# 01SignalDetect.net
KiCad netlist of a schematic drawn in Altium Designer
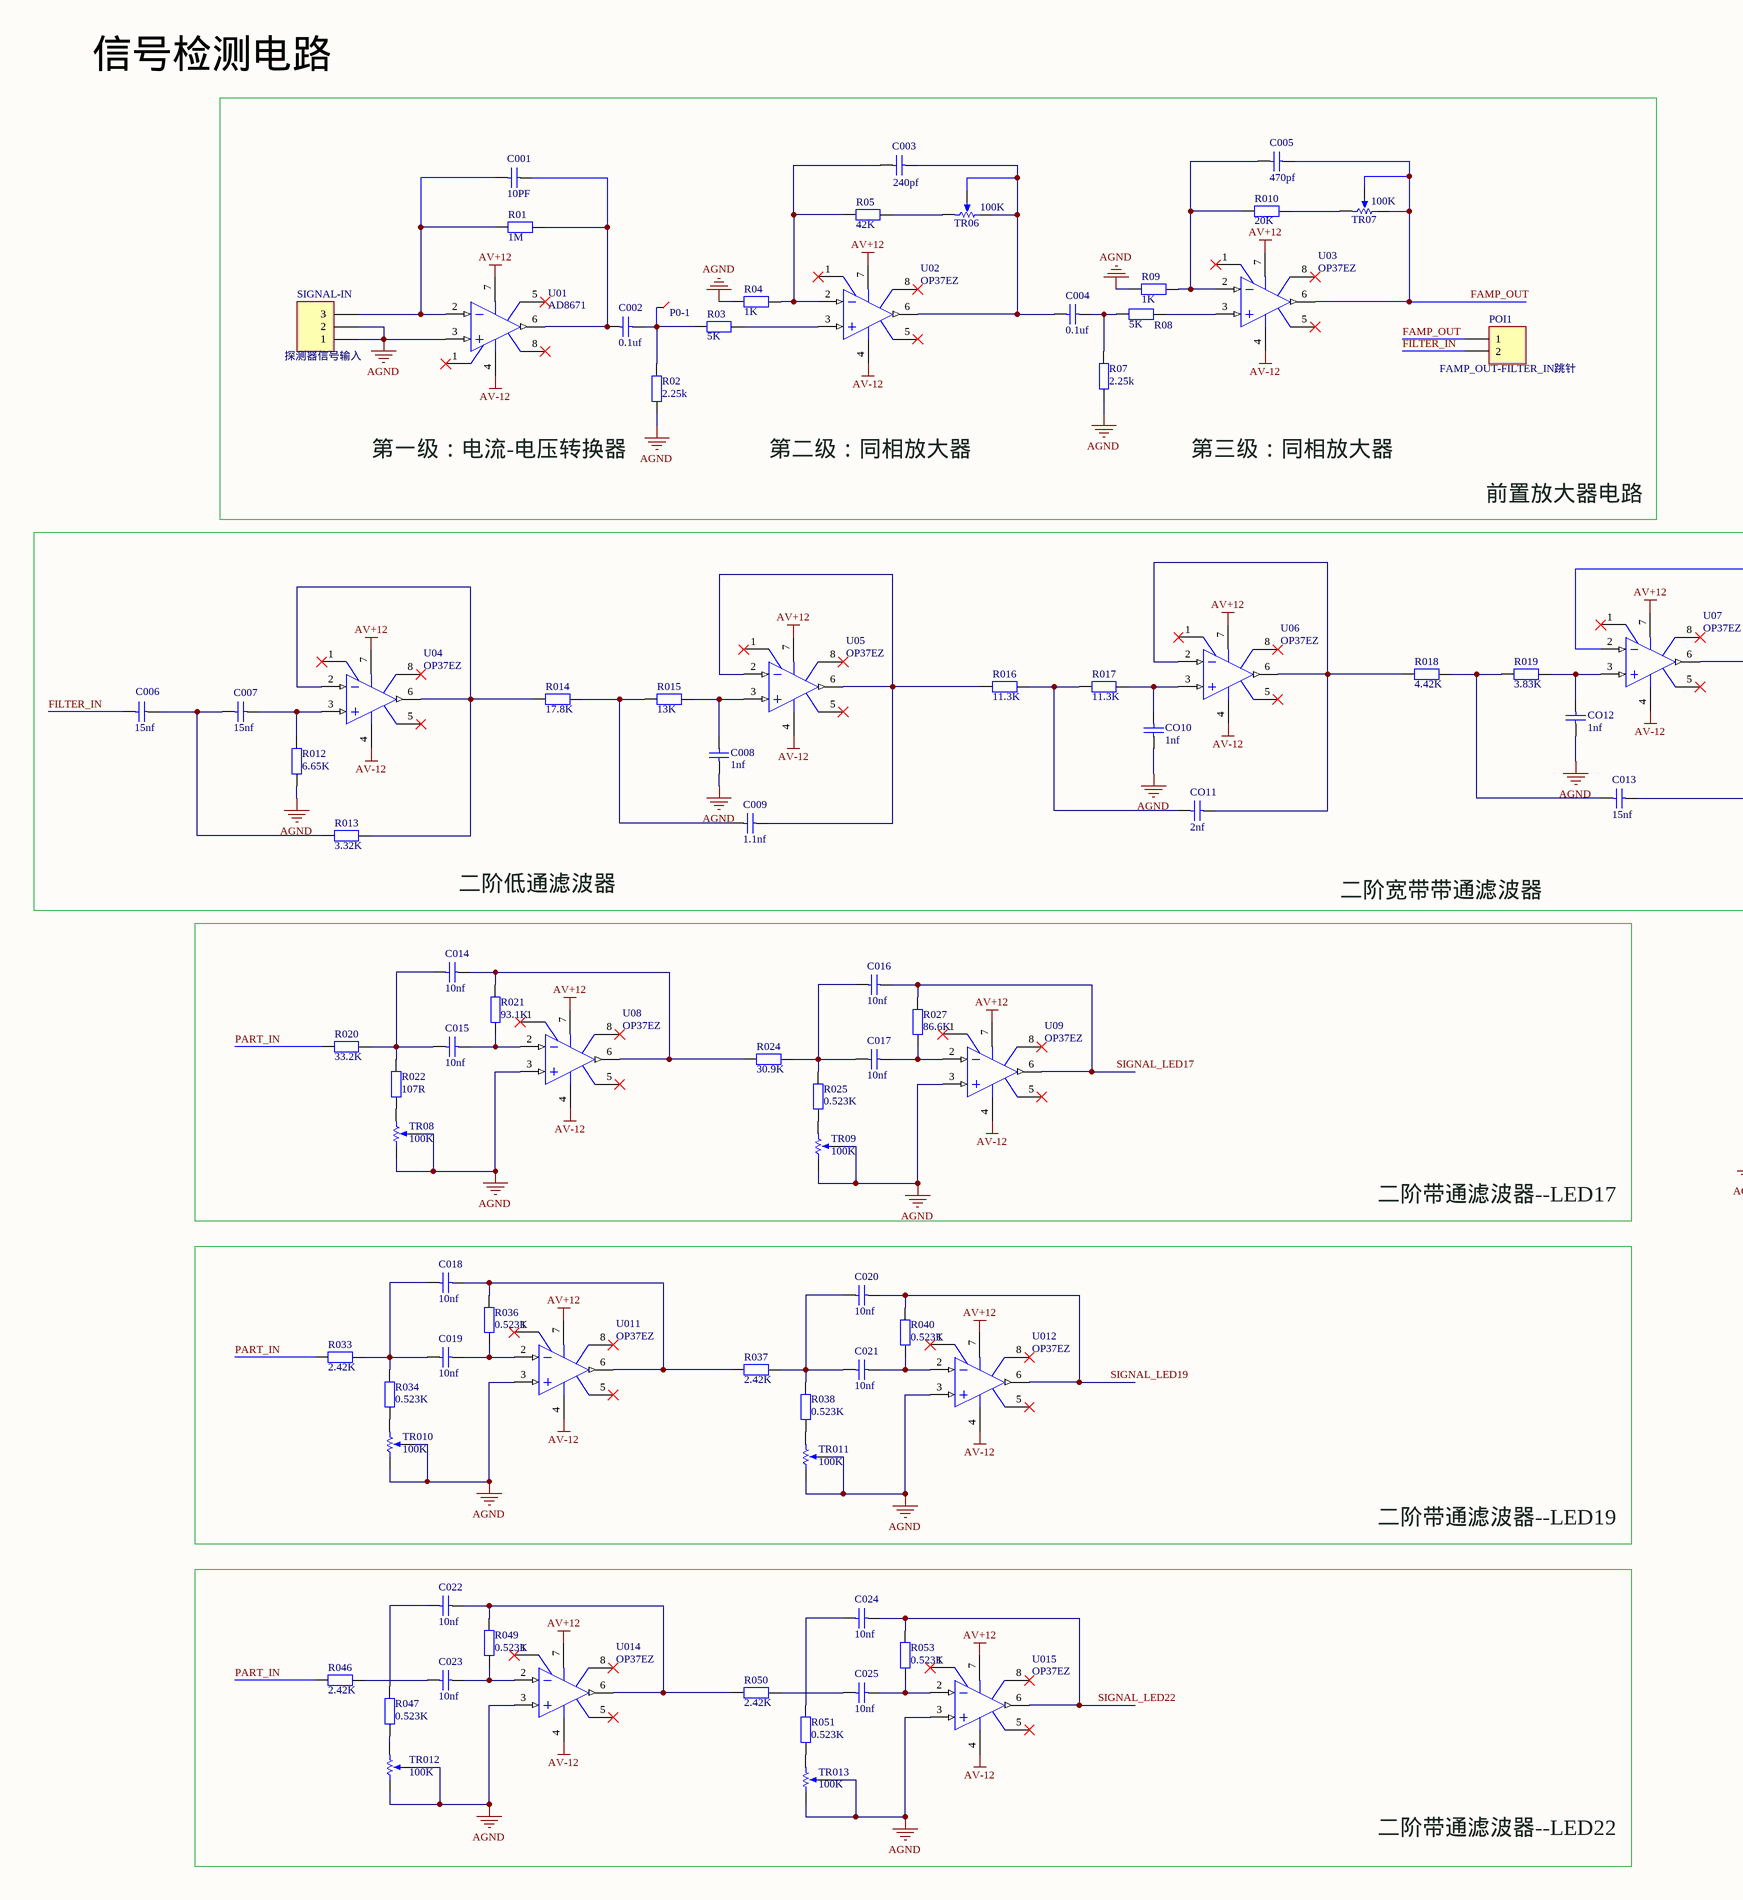
[diagram p0: 01SignalDetect.SchDoc, left]
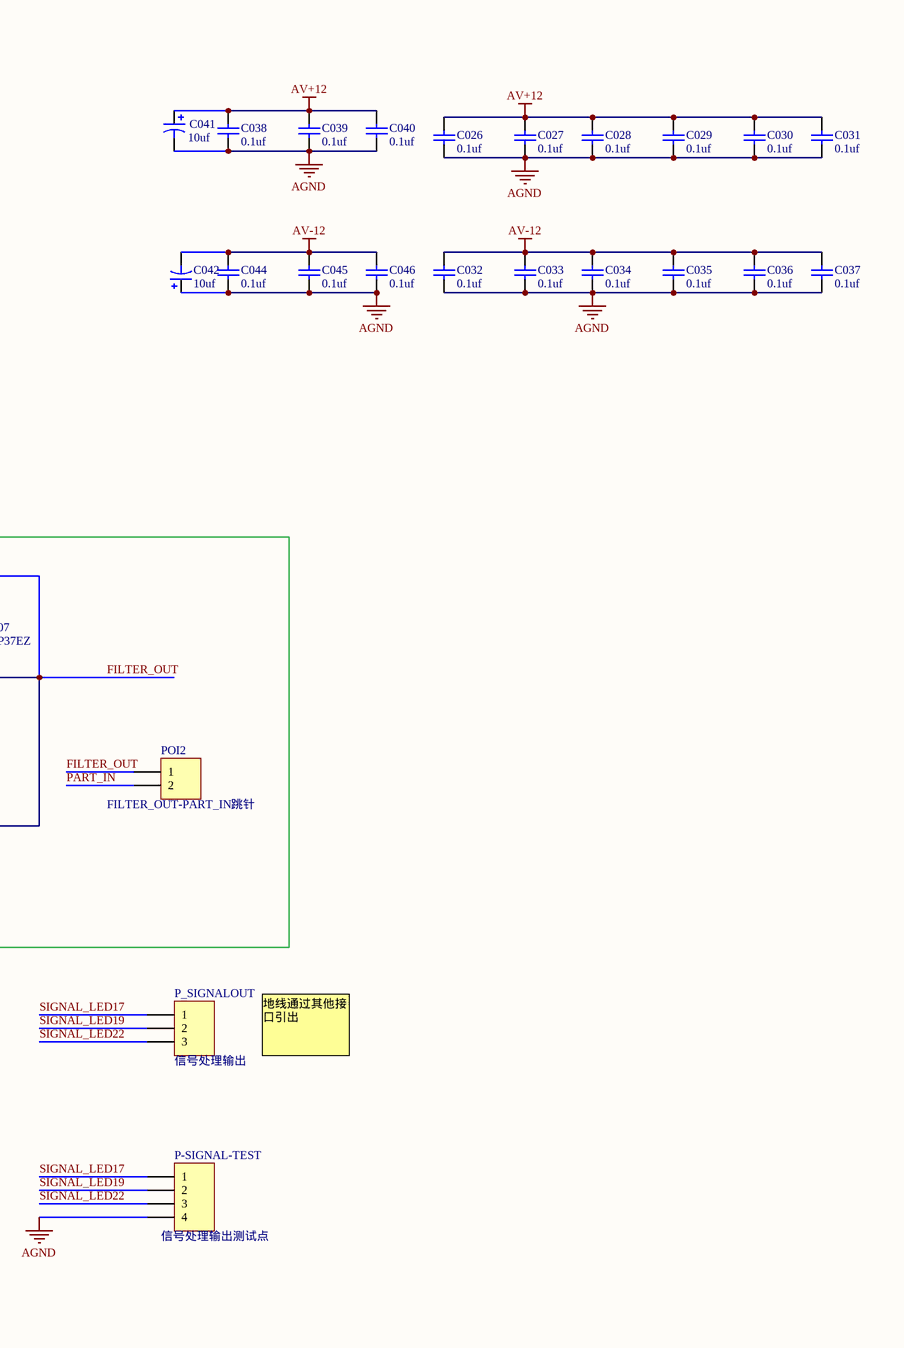
[diagram p1: 01SignalDetect.SchDoc, right]

(export (version "E")
  (design (tool "Eeschema 10.0.6"))
  (components
    (comp (ref "C001")
      (value "10PF")
      (footprint "CC0805")
      (description "Capacitor")
      (fields (field (name "Comment") "Cap"))
      (libsource (lib "Miscellaneous Devices") (part "Cap"))
    )
    (comp (ref "C002")
      (value "0.1uf")
      (footprint "CC0805")
      (description "Capacitor")
      (fields (field (name "Comment") "Cap"))
      (libsource (lib "Miscellaneous Devices") (part "Cap"))
    )
    (comp (ref "C003")
      (value "240pf")
      (footprint "CC0805")
      (description "Capacitor")
      (fields (field (name "Comment") "Cap"))
      (libsource (lib "Miscellaneous Devices") (part "Cap"))
    )
    (comp (ref "C004")
      (value "0.1uf")
      (footprint "CC0805")
      (description "Capacitor")
      (fields (field (name "Comment") "Cap"))
      (libsource (lib "Miscellaneous Devices") (part "Cap"))
    )
    (comp (ref "C005")
      (value "470pf")
      (footprint "CC0805")
      (description "Capacitor")
      (fields (field (name "Comment") "Cap"))
      (libsource (lib "Miscellaneous Devices") (part "Cap"))
    )
    (comp (ref "C006")
      (value "15nf")
      (footprint "CC0805")
      (description "Capacitor")
      (fields (field (name "Comment") "Cap"))
      (libsource (lib "Miscellaneous Devices") (part "Cap"))
    )
    (comp (ref "C007")
      (value "15nf")
      (footprint "CC0805")
      (description "Capacitor")
      (fields (field (name "Comment") "Cap"))
      (libsource (lib "Miscellaneous Devices") (part "Cap"))
    )
    (comp (ref "C008")
      (value "1nf")
      (footprint "CC0805")
      (description "Capacitor")
      (fields (field (name "Comment") "Cap"))
      (libsource (lib "Miscellaneous Devices") (part "Cap"))
    )
    (comp (ref "C009")
      (value "1.1nf")
      (footprint "CC0805")
      (description "Capacitor")
      (fields (field (name "Comment") "Cap"))
      (libsource (lib "Miscellaneous Devices") (part "Cap"))
    )
    (comp (ref "C013")
      (value "15nf")
      (footprint "CC0805")
      (description "Capacitor")
      (fields (field (name "Comment") "Cap"))
      (libsource (lib "Miscellaneous Devices") (part "Cap"))
    )
    (comp (ref "C014")
      (value "10nf")
      (footprint "校正电容")
      (description "Capacitor")
      (fields (field (name "Comment") "Cap"))
      (libsource (lib "Miscellaneous Devices") (part "Cap"))
    )
    (comp (ref "C015")
      (value "10nf")
      (footprint "校正电容")
      (description "Capacitor")
      (fields (field (name "Comment") "Cap"))
      (libsource (lib "Miscellaneous Devices") (part "Cap"))
    )
    (comp (ref "C016")
      (value "10nf")
      (footprint "校正电容")
      (description "Capacitor")
      (fields (field (name "Comment") "Cap"))
      (libsource (lib "Miscellaneous Devices") (part "Cap"))
    )
    (comp (ref "C017")
      (value "10nf")
      (footprint "校正电容")
      (description "Capacitor")
      (fields (field (name "Comment") "Cap"))
      (libsource (lib "Miscellaneous Devices") (part "Cap"))
    )
    (comp (ref "C018")
      (value "10nf")
      (footprint "校正电容")
      (description "Capacitor")
      (fields (field (name "Comment") "Cap"))
      (libsource (lib "Miscellaneous Devices") (part "Cap"))
    )
    (comp (ref "C019")
      (value "10nf")
      (footprint "校正电容")
      (description "Capacitor")
      (fields (field (name "Comment") "Cap"))
      (libsource (lib "Miscellaneous Devices") (part "Cap"))
    )
    (comp (ref "C020")
      (value "10nf")
      (footprint "校正电容")
      (description "Capacitor")
      (fields (field (name "Comment") "Cap"))
      (libsource (lib "Miscellaneous Devices") (part "Cap"))
    )
    (comp (ref "C021")
      (value "10nf")
      (footprint "校正电容")
      (description "Capacitor")
      (fields (field (name "Comment") "Cap"))
      (libsource (lib "Miscellaneous Devices") (part "Cap"))
    )
    (comp (ref "C022")
      (value "10nf")
      (footprint "校正电容")
      (description "Capacitor")
      (fields (field (name "Comment") "Cap"))
      (libsource (lib "Miscellaneous Devices") (part "Cap"))
    )
    (comp (ref "C023")
      (value "10nf")
      (footprint "校正电容")
      (description "Capacitor")
      (fields (field (name "Comment") "Cap"))
      (libsource (lib "Miscellaneous Devices") (part "Cap"))
    )
    (comp (ref "C024")
      (value "10nf")
      (footprint "校正电容")
      (description "Capacitor")
      (fields (field (name "Comment") "Cap"))
      (libsource (lib "Miscellaneous Devices") (part "Cap"))
    )
    (comp (ref "C025")
      (value "10nf")
      (footprint "校正电容")
      (description "Capacitor")
      (fields (field (name "Comment") "Cap"))
      (libsource (lib "Miscellaneous Devices") (part "Cap"))
    )
    (comp (ref "C026")
      (value "0.1uf")
      (footprint "CC0805")
      (description "Capacitor")
      (fields (field (name "Comment") "Cap"))
      (libsource (lib "Miscellaneous Devices") (part "Cap"))
    )
    (comp (ref "C027")
      (value "0.1uf")
      (footprint "CC0805")
      (description "Capacitor")
      (fields (field (name "Comment") "Cap"))
      (libsource (lib "Miscellaneous Devices") (part "Cap"))
    )
    (comp (ref "C028")
      (value "0.1uf")
      (footprint "CC0805")
      (description "Capacitor")
      (fields (field (name "Comment") "Cap"))
      (libsource (lib "Miscellaneous Devices") (part "Cap"))
    )
    (comp (ref "C029")
      (value "0.1uf")
      (footprint "CC0805")
      (description "Capacitor")
      (fields (field (name "Comment") "Cap"))
      (libsource (lib "Miscellaneous Devices") (part "Cap"))
    )
    (comp (ref "C030")
      (value "0.1uf")
      (footprint "CC0805")
      (description "Capacitor")
      (fields (field (name "Comment") "Cap"))
      (libsource (lib "Miscellaneous Devices") (part "Cap"))
    )
    (comp (ref "C031")
      (value "0.1uf")
      (footprint "CC0805")
      (description "Capacitor")
      (fields (field (name "Comment") "Cap"))
      (libsource (lib "Miscellaneous Devices") (part "Cap"))
    )
    (comp (ref "C032")
      (value "0.1uf")
      (footprint "CC0805")
      (description "Capacitor")
      (fields (field (name "Comment") "Cap"))
      (libsource (lib "Miscellaneous Devices") (part "Cap"))
    )
    (comp (ref "C033")
      (value "0.1uf")
      (footprint "CC0805")
      (description "Capacitor")
      (fields (field (name "Comment") "Cap"))
      (libsource (lib "Miscellaneous Devices") (part "Cap"))
    )
    (comp (ref "C034")
      (value "0.1uf")
      (footprint "CC0805")
      (description "Capacitor")
      (fields (field (name "Comment") "Cap"))
      (libsource (lib "Miscellaneous Devices") (part "Cap"))
    )
    (comp (ref "C035")
      (value "0.1uf")
      (footprint "CC0805")
      (description "Capacitor")
      (fields (field (name "Comment") "Cap"))
      (libsource (lib "Miscellaneous Devices") (part "Cap"))
    )
    (comp (ref "C036")
      (value "0.1uf")
      (footprint "CC0805")
      (description "Capacitor")
      (fields (field (name "Comment") "Cap"))
      (libsource (lib "Miscellaneous Devices") (part "Cap"))
    )
    (comp (ref "C037")
      (value "0.1uf")
      (footprint "CC0805")
      (description "Capacitor")
      (fields (field (name "Comment") "Cap"))
      (libsource (lib "Miscellaneous Devices") (part "Cap"))
    )
    (comp (ref "C038")
      (value "0.1uf")
      (footprint "CC0805")
      (description "Capacitor")
      (fields (field (name "Comment") "Cap"))
      (libsource (lib "Miscellaneous Devices") (part "Cap"))
    )
    (comp (ref "C039")
      (value "0.1uf")
      (footprint "CC0805")
      (description "Capacitor")
      (fields (field (name "Comment") "Cap"))
      (libsource (lib "Miscellaneous Devices") (part "Cap"))
    )
    (comp (ref "C040")
      (value "0.1uf")
      (footprint "CC0805")
      (description "Capacitor")
      (fields (field (name "Comment") "Cap"))
      (libsource (lib "Miscellaneous Devices") (part "Cap"))
    )
    (comp (ref "C041")
      (value "10uf")
      (footprint "4*4.5 贴片电解电容")
      (description "Polarized Capacitor (Radial)")
      (fields (field (name "Comment") "Cap Pol1"))
      (libsource (lib "Miscellaneous Devices") (part "Cap Pol1"))
    )
    (comp (ref "C042")
      (value "10uf")
      (footprint "4*4.5 贴片电解电容")
      (description "Polarized Capacitor (Radial)")
      (fields (field (name "Comment") "Cap Pol1"))
      (libsource (lib "Miscellaneous Devices") (part "Cap Pol1"))
    )
    (comp (ref "C044")
      (value "0.1uf")
      (footprint "CC0805")
      (description "Capacitor")
      (fields (field (name "Comment") "Cap"))
      (libsource (lib "Miscellaneous Devices") (part "Cap"))
    )
    (comp (ref "C045")
      (value "0.1uf")
      (footprint "CC0805")
      (description "Capacitor")
      (fields (field (name "Comment") "Cap"))
      (libsource (lib "Miscellaneous Devices") (part "Cap"))
    )
    (comp (ref "C046")
      (value "0.1uf")
      (footprint "CC0805")
      (description "Capacitor")
      (fields (field (name "Comment") "Cap"))
      (libsource (lib "Miscellaneous Devices") (part "Cap"))
    )
    (comp (ref "CO10")
      (value "1nf")
      (footprint "CC0805")
      (description "Capacitor")
      (fields (field (name "Comment") "Cap"))
      (libsource (lib "Miscellaneous Devices") (part "Cap"))
    )
    (comp (ref "CO11")
      (value "2nf")
      (footprint "CC0805")
      (description "Capacitor")
      (fields (field (name "Comment") "Cap"))
      (libsource (lib "Miscellaneous Devices") (part "Cap"))
    )
    (comp (ref "CO12")
      (value "1nf")
      (footprint "CC0805")
      (description "Capacitor")
      (fields (field (name "Comment") "Cap"))
      (libsource (lib "Miscellaneous Devices") (part "Cap"))
    )
    (comp (ref "P-SIGNAL-TEST")
      (value "信号处理输出测试点")
      (footprint "HDR1X4")
      (description "Header, 4-Pin")
      (libsource (lib "Miscellaneous Connectors") (part "Header 4"))
    )
    (comp (ref "P0-1") (value "测试点") (footprint "Text_PAD") (libsource (lib "MY device0") (part "测试点")))
    (comp (ref "POI1")
      (value "FAMP_OUT-FILTER_IN跳针")
      (footprint "HDR1X2")
      (description "Header, 2-Pin")
      (libsource (lib "Miscellaneous Connectors") (part "Header 2"))
    )
    (comp (ref "POI2")
      (value "FILTER_OUT-PART_IN跳针")
      (footprint "HDR1X2")
      (description "Header, 2-Pin")
      (libsource (lib "Miscellaneous Connectors") (part "Header 2"))
    )
    (comp (ref "P_SIGNALOUT")
      (value "信号处理输出")
      (footprint "HDR1X3H")
      (description "Header, 3-Pin, Right Angle")
      (libsource (lib "Miscellaneous Connectors") (part "Header 3H"))
    )
    (comp (ref "R01")
      (value "1M")
      (footprint "0805")
      (description "Resistor")
      (fields (field (name "Comment") "Res2"))
      (libsource (lib "Miscellaneous Devices") (part "Res2"))
    )
    (comp (ref "R02")
      (value "2.25k")
      (footprint "0805")
      (description "Resistor")
      (fields (field (name "Comment") "Res2"))
      (libsource (lib "") (part "Res2_1"))
    )
    (comp (ref "R03")
      (value "5K")
      (footprint "0805")
      (description "Resistor")
      (fields (field (name "Comment") "Res2"))
      (libsource (lib "Miscellaneous Devices") (part "Res2"))
    )
    (comp (ref "R04")
      (value "1K")
      (footprint "0805")
      (description "Resistor")
      (fields (field (name "Comment") "Res2"))
      (libsource (lib "Miscellaneous Devices") (part "Res2"))
    )
    (comp (ref "R05")
      (value "42K")
      (footprint "0805")
      (description "Resistor")
      (fields (field (name "Comment") "Res2"))
      (libsource (lib "Miscellaneous Devices") (part "Res2"))
    )
    (comp (ref "R07")
      (value "2.25k")
      (footprint "0805")
      (description "Resistor")
      (fields (field (name "Comment") "Res2"))
      (libsource (lib "") (part "Res2_1"))
    )
    (comp (ref "R08")
      (value "5K")
      (footprint "0805")
      (description "Resistor")
      (fields (field (name "Comment") "Res2"))
      (libsource (lib "Miscellaneous Devices") (part "Res2"))
    )
    (comp (ref "R09")
      (value "1K")
      (footprint "0805")
      (description "Resistor")
      (fields (field (name "Comment") "Res2"))
      (libsource (lib "Miscellaneous Devices") (part "Res2"))
    )
    (comp (ref "R010")
      (value "20K")
      (footprint "0805")
      (description "Resistor")
      (fields (field (name "Comment") "Res2"))
      (libsource (lib "Miscellaneous Devices") (part "Res2"))
    )
    (comp (ref "R012")
      (value "6.65K")
      (footprint "0805")
      (description "Resistor")
      (fields (field (name "Comment") "Res2"))
      (libsource (lib "") (part "Res2_1"))
    )
    (comp (ref "R013")
      (value "3.32K")
      (footprint "0805")
      (description "Resistor")
      (fields (field (name "Comment") "Res2"))
      (libsource (lib "") (part "Res2_2"))
    )
    (comp (ref "R014")
      (value "17.8K")
      (footprint "0805")
      (description "Resistor")
      (fields (field (name "Comment") "Res2"))
      (libsource (lib "Miscellaneous Devices") (part "Res2"))
    )
    (comp (ref "R015")
      (value "13K")
      (footprint "0805")
      (description "Resistor")
      (fields (field (name "Comment") "Res2"))
      (libsource (lib "") (part "Res2_2"))
    )
    (comp (ref "R016")
      (value "11.3K")
      (footprint "0805")
      (description "Resistor")
      (fields (field (name "Comment") "Res2"))
      (libsource (lib "Miscellaneous Devices") (part "Res2"))
    )
    (comp (ref "R017")
      (value "11.3K")
      (footprint "0805")
      (description "Resistor")
      (fields (field (name "Comment") "Res2"))
      (libsource (lib "Miscellaneous Devices") (part "Res2"))
    )
    (comp (ref "R018")
      (value "4.42K")
      (footprint "0805")
      (description "Resistor")
      (fields (field (name "Comment") "Res2"))
      (libsource (lib "Miscellaneous Devices") (part "Res2"))
    )
    (comp (ref "R019")
      (value "3.83K")
      (footprint "0805")
      (description "Resistor")
      (fields (field (name "Comment") "Res2"))
      (libsource (lib "Miscellaneous Devices") (part "Res2"))
    )
    (comp (ref "R020")
      (value "33.2K")
      (footprint "0805")
      (description "Resistor")
      (fields (field (name "Comment") "Res2"))
      (libsource (lib "Miscellaneous Devices") (part "Res2"))
    )
    (comp (ref "R021")
      (value "93.1K")
      (footprint "0805")
      (description "Resistor")
      (fields (field (name "Comment") "Res2"))
      (libsource (lib "") (part "Res2_1"))
    )
    (comp (ref "R022")
      (value "107R")
      (footprint "0805")
      (description "Resistor")
      (fields (field (name "Comment") "Res2"))
      (libsource (lib "") (part "Res2_1"))
    )
    (comp (ref "R024")
      (value "30.9K")
      (footprint "0805")
      (description "Resistor")
      (fields (field (name "Comment") "Res2"))
      (libsource (lib "Miscellaneous Devices") (part "Res2"))
    )
    (comp (ref "R025")
      (value "0.523K")
      (footprint "0805")
      (description "Resistor")
      (fields (field (name "Comment") "Res2"))
      (libsource (lib "") (part "Res2_1"))
    )
    (comp (ref "R027")
      (value "86.6K")
      (footprint "0805")
      (description "Resistor")
      (fields (field (name "Comment") "Res2"))
      (libsource (lib "") (part "Res2_1"))
    )
    (comp (ref "R033")
      (value "2.42K")
      (footprint "0805")
      (description "Resistor")
      (fields (field (name "Comment") "Res2"))
      (libsource (lib "Miscellaneous Devices") (part "Res2"))
    )
    (comp (ref "R034")
      (value "0.523K")
      (footprint "0805")
      (description "Resistor")
      (fields (field (name "Comment") "Res2"))
      (libsource (lib "") (part "Res2_1"))
    )
    (comp (ref "R036")
      (value "0.523K")
      (footprint "0805")
      (description "Resistor")
      (fields (field (name "Comment") "Res2"))
      (libsource (lib "") (part "Res2_1"))
    )
    (comp (ref "R037")
      (value "2.42K")
      (footprint "0805")
      (description "Resistor")
      (fields (field (name "Comment") "Res2"))
      (libsource (lib "Miscellaneous Devices") (part "Res2"))
    )
    (comp (ref "R038")
      (value "0.523K")
      (footprint "0805")
      (description "Resistor")
      (fields (field (name "Comment") "Res2"))
      (libsource (lib "") (part "Res2_1"))
    )
    (comp (ref "R040")
      (value "0.523K")
      (footprint "0805")
      (description "Resistor")
      (fields (field (name "Comment") "Res2"))
      (libsource (lib "") (part "Res2_1"))
    )
    (comp (ref "R046")
      (value "2.42K")
      (footprint "0805")
      (description "Resistor")
      (fields (field (name "Comment") "Res2"))
      (libsource (lib "Miscellaneous Devices") (part "Res2"))
    )
    (comp (ref "R047")
      (value "0.523K")
      (footprint "0805")
      (description "Resistor")
      (fields (field (name "Comment") "Res2"))
      (libsource (lib "") (part "Res2_1"))
    )
    (comp (ref "R049")
      (value "0.523K")
      (footprint "0805")
      (description "Resistor")
      (fields (field (name "Comment") "Res2"))
      (libsource (lib "") (part "Res2_1"))
    )
    (comp (ref "R050")
      (value "2.42K")
      (footprint "0805")
      (description "Resistor")
      (fields (field (name "Comment") "Res2"))
      (libsource (lib "Miscellaneous Devices") (part "Res2"))
    )
    (comp (ref "R051")
      (value "0.523K")
      (footprint "0805")
      (description "Resistor")
      (fields (field (name "Comment") "Res2"))
      (libsource (lib "") (part "Res2_1"))
    )
    (comp (ref "R053")
      (value "0.523K")
      (footprint "0805")
      (description "Resistor")
      (fields (field (name "Comment") "Res2"))
      (libsource (lib "") (part "Res2_1"))
    )
    (comp (ref "SIGNAL-IN")
      (value "探测器信号输入")
      (footprint "HDR1X3H")
      (description "Header, 3-Pin, Right Angle")
      (libsource (lib "") (part "Header 3H_1"))
    )
    (comp (ref "TR06")
      (value "100K")
      (footprint "VR5")
      (description "Potentiometer")
      (fields (field (name "Comment") "RPot"))
      (libsource (lib "Miscellaneous Devices") (part "RPot"))
    )
    (comp (ref "TR07")
      (value "100K")
      (footprint "VR5")
      (description "Potentiometer")
      (fields (field (name "Comment") "RPot"))
      (libsource (lib "Miscellaneous Devices") (part "RPot"))
    )
    (comp (ref "TR08")
      (value "100K")
      (footprint "VR5")
      (description "Potentiometer")
      (fields (field (name "Comment") "RPot"))
      (libsource (lib "Miscellaneous Devices") (part "RPot"))
    )
    (comp (ref "TR09")
      (value "100K")
      (footprint "VR5")
      (description "Potentiometer")
      (fields (field (name "Comment") "RPot"))
      (libsource (lib "Miscellaneous Devices") (part "RPot"))
    )
    (comp (ref "TR010")
      (value "100K")
      (footprint "VR5")
      (description "Potentiometer")
      (fields (field (name "Comment") "RPot"))
      (libsource (lib "Miscellaneous Devices") (part "RPot"))
    )
    (comp (ref "TR011")
      (value "100K")
      (footprint "VR5")
      (description "Potentiometer")
      (fields (field (name "Comment") "RPot"))
      (libsource (lib "Miscellaneous Devices") (part "RPot"))
    )
    (comp (ref "TR012")
      (value "100K")
      (footprint "VR5")
      (description "Potentiometer")
      (fields (field (name "Comment") "RPot"))
      (libsource (lib "Miscellaneous Devices") (part "RPot"))
    )
    (comp (ref "TR013")
      (value "100K")
      (footprint "VR5")
      (description "Potentiometer")
      (fields (field (name "Comment") "RPot"))
      (libsource (lib "Miscellaneous Devices") (part "RPot"))
    )
    (comp (ref "U01")
      (value "AD8671")
      (footprint "SO-8-N")
      (description "Low-Noise, Precision Operational Amplifier")
      (libsource (lib "AD Operational Amplifier") (part "OP27FJ"))
    )
    (comp (ref "U02")
      (value "OP37EZ")
      (footprint "SO-8-N")
      (description "Low-Noise, Precision, High-Speed Operational Amplifier (Avcl >= 5)")
      (libsource (lib "AD Operational Amplifier") (part "OP37EZ"))
    )
    (comp (ref "U03")
      (value "OP37EZ")
      (footprint "SO-8-N")
      (description "Low-Noise, Precision, High-Speed Operational Amplifier (Avcl >= 5)")
      (libsource (lib "AD Operational Amplifier") (part "OP37EZ"))
    )
    (comp (ref "U04")
      (value "OP37EZ")
      (footprint "SO-8-N")
      (description "Low-Noise, Precision, High-Speed Operational Amplifier (Avcl >= 5)")
      (libsource (lib "AD Operational Amplifier") (part "OP37EZ"))
    )
    (comp (ref "U05")
      (value "OP37EZ")
      (footprint "SO-8-N")
      (description "Low-Noise, Precision, High-Speed Operational Amplifier (Avcl >= 5)")
      (libsource (lib "AD Operational Amplifier") (part "OP37EZ"))
    )
    (comp (ref "U06")
      (value "OP37EZ")
      (footprint "SO-8-N")
      (description "Low-Noise, Precision, High-Speed Operational Amplifier (Avcl >= 5)")
      (libsource (lib "AD Operational Amplifier") (part "OP37EZ"))
    )
    (comp (ref "U07")
      (value "OP37EZ")
      (footprint "SO-8-N")
      (description "Low-Noise, Precision, High-Speed Operational Amplifier (Avcl >= 5)")
      (libsource (lib "AD Operational Amplifier") (part "OP37EZ"))
    )
    (comp (ref "U08")
      (value "OP37EZ")
      (footprint "SO-8-N")
      (description "Low-Noise, Precision, High-Speed Operational Amplifier (Avcl >= 5)")
      (libsource (lib "AD Operational Amplifier") (part "OP37EZ"))
    )
    (comp (ref "U09")
      (value "OP37EZ")
      (footprint "SO-8-N")
      (description "Low-Noise, Precision, High-Speed Operational Amplifier (Avcl >= 5)")
      (libsource (lib "AD Operational Amplifier") (part "OP37EZ"))
    )
    (comp (ref "U011")
      (value "OP37EZ")
      (footprint "SO-8-N")
      (description "Low-Noise, Precision, High-Speed Operational Amplifier (Avcl >= 5)")
      (libsource (lib "AD Operational Amplifier") (part "OP37EZ"))
    )
    (comp (ref "U012")
      (value "OP37EZ")
      (footprint "SO-8-N")
      (description "Low-Noise, Precision, High-Speed Operational Amplifier (Avcl >= 5)")
      (libsource (lib "AD Operational Amplifier") (part "OP37EZ"))
    )
    (comp (ref "U014")
      (value "OP37EZ")
      (footprint "SO-8-N")
      (description "Low-Noise, Precision, High-Speed Operational Amplifier (Avcl >= 5)")
      (libsource (lib "AD Operational Amplifier") (part "OP37EZ"))
    )
    (comp (ref "U015")
      (value "OP37EZ")
      (footprint "SO-8-N")
      (description "Low-Noise, Precision, High-Speed Operational Amplifier (Avcl >= 5)")
      (libsource (lib "AD Operational Amplifier") (part "OP37EZ"))
    )
  )
  (nets
    (net (code "1") (name "/FAMP_OUT") (class "Default")
      (node (ref "C005") (pin "1") (pinfunction "1_1") (pintype "passive"))
      (node (ref "POI1") (pin "1") (pinfunction "1_1") (pintype "passive"))
      (node (ref "TR07") (pin "1") (pinfunction "TOP_1") (pintype "passive"))
      (node (ref "TR07") (pin "2") (pinfunction "TAP_2") (pintype "passive"))
      (node (ref "U03") (pin "6") (pinfunction "OUT_6") (pintype "output"))
    )
    (net (code "2") (name "/FILTER_IN") (class "Default")
      (node (ref "C006") (pin "2") (pinfunction "2_2") (pintype "passive"))
      (node (ref "POI1") (pin "2") (pinfunction "2_2") (pintype "passive"))
    )
    (net (code "3") (name "/FILTER_OUT") (class "Default")
      (node (ref "C013") (pin "1") (pinfunction "1_1") (pintype "passive"))
      (node (ref "POI2") (pin "1") (pinfunction "1_1") (pintype "passive"))
      (node (ref "U07") (pin "2") (pinfunction "IN-_2") (pintype "input"))
      (node (ref "U07") (pin "6") (pinfunction "OUT_6") (pintype "output"))
    )
    (net (code "4") (name "/PART_IN") (class "Default")
      (node (ref "POI2") (pin "2") (pinfunction "2_2") (pintype "passive"))
      (node (ref "R020") (pin "1") (pinfunction "1_1") (pintype "passive"))
      (node (ref "R033") (pin "1") (pinfunction "1_1") (pintype "passive"))
      (node (ref "R046") (pin "1") (pinfunction "1_1") (pintype "passive"))
    )
    (net (code "5") (name "/SIGNAL_LED17") (class "Default")
      (node (ref "C016") (pin "1") (pinfunction "1_1") (pintype "passive"))
      (node (ref "P-SIGNAL-TEST") (pin "1") (pinfunction "1_1") (pintype "passive"))
      (node (ref "P_SIGNALOUT") (pin "1") (pinfunction "1_1") (pintype "passive"))
      (node (ref "R027") (pin "2") (pinfunction "2_2") (pintype "passive"))
      (node (ref "U09") (pin "6") (pinfunction "OUT_6") (pintype "output"))
    )
    (net (code "6") (name "/SIGNAL_LED19") (class "Default")
      (node (ref "C020") (pin "1") (pinfunction "1_1") (pintype "passive"))
      (node (ref "P-SIGNAL-TEST") (pin "2") (pinfunction "2_2") (pintype "passive"))
      (node (ref "P_SIGNALOUT") (pin "2") (pinfunction "2_2") (pintype "passive"))
      (node (ref "R040") (pin "2") (pinfunction "2_2") (pintype "passive"))
      (node (ref "U012") (pin "6") (pinfunction "OUT_6") (pintype "output"))
    )
    (net (code "7") (name "/SIGNAL_LED22") (class "Default")
      (node (ref "C024") (pin "1") (pinfunction "1_1") (pintype "passive"))
      (node (ref "P-SIGNAL-TEST") (pin "3") (pinfunction "3_3") (pintype "passive"))
      (node (ref "P_SIGNALOUT") (pin "3") (pinfunction "3_3") (pintype "passive"))
      (node (ref "R053") (pin "2") (pinfunction "2_2") (pintype "passive"))
      (node (ref "U015") (pin "6") (pinfunction "OUT_6") (pintype "output"))
    )
    (net (code "8") (name "AGND") (class "Default")
      (node (ref "C008") (pin "2") (pinfunction "2_2") (pintype "passive"))
      (node (ref "C026") (pin "2") (pinfunction "2_2") (pintype "passive"))
      (node (ref "C027") (pin "2") (pinfunction "2_2") (pintype "passive"))
      (node (ref "C028") (pin "2") (pinfunction "2_2") (pintype "passive"))
      (node (ref "C029") (pin "2") (pinfunction "2_2") (pintype "passive"))
      (node (ref "C030") (pin "2") (pinfunction "2_2") (pintype "passive"))
      (node (ref "C031") (pin "2") (pinfunction "2_2") (pintype "passive"))
      (node (ref "C032") (pin "2") (pinfunction "2_2") (pintype "passive"))
      (node (ref "C033") (pin "2") (pinfunction "2_2") (pintype "passive"))
      (node (ref "C034") (pin "2") (pinfunction "2_2") (pintype "passive"))
      (node (ref "C035") (pin "2") (pinfunction "2_2") (pintype "passive"))
      (node (ref "C036") (pin "2") (pinfunction "2_2") (pintype "passive"))
      (node (ref "C037") (pin "2") (pinfunction "2_2") (pintype "passive"))
      (node (ref "C038") (pin "2") (pinfunction "2_2") (pintype "passive"))
      (node (ref "C039") (pin "2") (pinfunction "2_2") (pintype "passive"))
      (node (ref "C040") (pin "2") (pinfunction "2_2") (pintype "passive"))
      (node (ref "C041") (pin "2") (pinfunction "2_2") (pintype "passive"))
      (node (ref "C042") (pin "1") (pinfunction "1_1") (pintype "passive"))
      (node (ref "C044") (pin "2") (pinfunction "2_2") (pintype "passive"))
      (node (ref "C045") (pin "2") (pinfunction "2_2") (pintype "passive"))
      (node (ref "C046") (pin "2") (pinfunction "2_2") (pintype "passive"))
      (node (ref "CO10") (pin "1") (pinfunction "1_1") (pintype "passive"))
      (node (ref "CO12") (pin "1") (pinfunction "1_1") (pintype "passive"))
      (node (ref "P-SIGNAL-TEST") (pin "4") (pinfunction "4_4") (pintype "passive"))
      (node (ref "R012") (pin "1") (pinfunction "1_1") (pintype "passive"))
      (node (ref "R02") (pin "1") (pinfunction "1_1") (pintype "passive"))
      (node (ref "R04") (pin "1") (pinfunction "1_1") (pintype "passive"))
      (node (ref "R07") (pin "1") (pinfunction "1_1") (pintype "passive"))
      (node (ref "R09") (pin "1") (pinfunction "1_1") (pintype "passive"))
      (node (ref "SIGNAL-IN") (pin "1") (pinfunction "1_1") (pintype "passive"))
      (node (ref "SIGNAL-IN") (pin "2") (pinfunction "2_2") (pintype "passive"))
      (node (ref "TR010") (pin "1") (pinfunction "TOP_1") (pintype "passive"))
      (node (ref "TR010") (pin "2") (pinfunction "TAP_2") (pintype "passive"))
      (node (ref "TR011") (pin "1") (pinfunction "TOP_1") (pintype "passive"))
      (node (ref "TR011") (pin "2") (pinfunction "TAP_2") (pintype "passive"))
      (node (ref "TR012") (pin "1") (pinfunction "TOP_1") (pintype "passive"))
      (node (ref "TR012") (pin "2") (pinfunction "TAP_2") (pintype "passive"))
      (node (ref "TR013") (pin "1") (pinfunction "TOP_1") (pintype "passive"))
      (node (ref "TR013") (pin "2") (pinfunction "TAP_2") (pintype "passive"))
      (node (ref "TR08") (pin "1") (pinfunction "TOP_1") (pintype "passive"))
      (node (ref "TR08") (pin "2") (pinfunction "TAP_2") (pintype "passive"))
      (node (ref "TR09") (pin "1") (pinfunction "TOP_1") (pintype "passive"))
      (node (ref "TR09") (pin "2") (pinfunction "TAP_2") (pintype "passive"))
      (node (ref "U01") (pin "3") (pinfunction "IN+_3") (pintype "input"))
      (node (ref "U011") (pin "3") (pinfunction "IN+_3") (pintype "input"))
      (node (ref "U012") (pin "3") (pinfunction "IN+_3") (pintype "input"))
      (node (ref "U014") (pin "3") (pinfunction "IN+_3") (pintype "input"))
      (node (ref "U015") (pin "3") (pinfunction "IN+_3") (pintype "input"))
      (node (ref "U08") (pin "3") (pinfunction "IN+_3") (pintype "input"))
      (node (ref "U09") (pin "3") (pinfunction "IN+_3") (pintype "input"))
    )
    (net (code "9") (name "AV+12") (class "Default")
      (node (ref "C026") (pin "1") (pinfunction "1_1") (pintype "passive"))
      (node (ref "C027") (pin "1") (pinfunction "1_1") (pintype "passive"))
      (node (ref "C028") (pin "1") (pinfunction "1_1") (pintype "passive"))
      (node (ref "C029") (pin "1") (pinfunction "1_1") (pintype "passive"))
      (node (ref "C030") (pin "1") (pinfunction "1_1") (pintype "passive"))
      (node (ref "C031") (pin "1") (pinfunction "1_1") (pintype "passive"))
      (node (ref "C038") (pin "1") (pinfunction "1_1") (pintype "passive"))
      (node (ref "C039") (pin "1") (pinfunction "1_1") (pintype "passive"))
      (node (ref "C040") (pin "1") (pinfunction "1_1") (pintype "passive"))
      (node (ref "C041") (pin "1") (pinfunction "1_1") (pintype "passive"))
      (node (ref "U01") (pin "7") (pinfunction "V+_7") (pintype "power_in"))
      (node (ref "U011") (pin "7") (pinfunction "V+_7") (pintype "power_in"))
      (node (ref "U012") (pin "7") (pinfunction "V+_7") (pintype "power_in"))
      (node (ref "U014") (pin "7") (pinfunction "V+_7") (pintype "power_in"))
      (node (ref "U015") (pin "7") (pinfunction "V+_7") (pintype "power_in"))
      (node (ref "U02") (pin "7") (pinfunction "V+_7") (pintype "power_in"))
      (node (ref "U03") (pin "7") (pinfunction "V+_7") (pintype "power_in"))
      (node (ref "U04") (pin "7") (pinfunction "V+_7") (pintype "power_in"))
      (node (ref "U05") (pin "7") (pinfunction "V+_7") (pintype "power_in"))
      (node (ref "U06") (pin "7") (pinfunction "V+_7") (pintype "power_in"))
      (node (ref "U07") (pin "7") (pinfunction "V+_7") (pintype "power_in"))
      (node (ref "U08") (pin "7") (pinfunction "V+_7") (pintype "power_in"))
      (node (ref "U09") (pin "7") (pinfunction "V+_7") (pintype "power_in"))
    )
    (net (code "10") (name "AV-12") (class "Default")
      (node (ref "C032") (pin "1") (pinfunction "1_1") (pintype "passive"))
      (node (ref "C033") (pin "1") (pinfunction "1_1") (pintype "passive"))
      (node (ref "C034") (pin "1") (pinfunction "1_1") (pintype "passive"))
      (node (ref "C035") (pin "1") (pinfunction "1_1") (pintype "passive"))
      (node (ref "C036") (pin "1") (pinfunction "1_1") (pintype "passive"))
      (node (ref "C037") (pin "1") (pinfunction "1_1") (pintype "passive"))
      (node (ref "C042") (pin "2") (pinfunction "2_2") (pintype "passive"))
      (node (ref "C044") (pin "1") (pinfunction "1_1") (pintype "passive"))
      (node (ref "C045") (pin "1") (pinfunction "1_1") (pintype "passive"))
      (node (ref "C046") (pin "1") (pinfunction "1_1") (pintype "passive"))
      (node (ref "U01") (pin "4") (pinfunction "V-_4") (pintype "power_in"))
      (node (ref "U011") (pin "4") (pinfunction "V-_4") (pintype "power_in"))
      (node (ref "U012") (pin "4") (pinfunction "V-_4") (pintype "power_in"))
      (node (ref "U014") (pin "4") (pinfunction "V-_4") (pintype "power_in"))
      (node (ref "U015") (pin "4") (pinfunction "V-_4") (pintype "power_in"))
      (node (ref "U02") (pin "4") (pinfunction "V-_4") (pintype "power_in"))
      (node (ref "U03") (pin "4") (pinfunction "V-_4") (pintype "power_in"))
      (node (ref "U04") (pin "4") (pinfunction "V-_4") (pintype "power_in"))
      (node (ref "U05") (pin "4") (pinfunction "V-_4") (pintype "power_in"))
      (node (ref "U06") (pin "4") (pinfunction "V-_4") (pintype "power_in"))
      (node (ref "U07") (pin "4") (pinfunction "V-_4") (pintype "power_in"))
      (node (ref "U08") (pin "4") (pinfunction "V-_4") (pintype "power_in"))
      (node (ref "U09") (pin "4") (pinfunction "V-_4") (pintype "power_in"))
    )
    (net (code "11") (name "Net-(C002-Pad1)") (class "Default")
      (node (ref "C002") (pin "1") (pinfunction "1_1") (pintype "passive"))
      (node (ref "P0-1") (pin "0") (pinfunction "0_0") (pintype "passive"))
      (node (ref "R02") (pin "2") (pinfunction "2_2") (pintype "passive"))
      (node (ref "R03") (pin "1") (pinfunction "1_1") (pintype "passive"))
    )
    (net (code "12") (name "Net-(C004-Pad1)") (class "Default")
      (node (ref "C004") (pin "1") (pinfunction "1_1") (pintype "passive"))
      (node (ref "R07") (pin "2") (pinfunction "2_2") (pintype "passive"))
      (node (ref "R08") (pin "1") (pinfunction "1_1") (pintype "passive"))
    )
    (net (code "13") (name "Net-(C006-Pad1)") (class "Default")
      (node (ref "C006") (pin "1") (pinfunction "1_1") (pintype "passive"))
      (node (ref "C007") (pin "2") (pinfunction "2_2") (pintype "passive"))
      (node (ref "R013") (pin "2") (pinfunction "2_2") (pintype "passive"))
    )
    (net (code "14") (name "Net-(C009-Pad2)") (class "Default")
      (node (ref "C009") (pin "2") (pinfunction "2_2") (pintype "passive"))
      (node (ref "R014") (pin "2") (pinfunction "2_2") (pintype "passive"))
      (node (ref "R015") (pin "2") (pinfunction "2_2") (pintype "passive"))
    )
    (net (code "15") (name "Net-(C013-Pad2)") (class "Default")
      (node (ref "C013") (pin "2") (pinfunction "2_2") (pintype "passive"))
      (node (ref "R018") (pin "2") (pinfunction "2_2") (pintype "passive"))
      (node (ref "R019") (pin "1") (pinfunction "1_1") (pintype "passive"))
    )
    (net (code "16") (name "Net-(C014-Pad2)") (class "Default")
      (node (ref "C014") (pin "2") (pinfunction "2_2") (pintype "passive"))
      (node (ref "C015") (pin "2") (pinfunction "2_2") (pintype "passive"))
      (node (ref "R020") (pin "2") (pinfunction "2_2") (pintype "passive"))
      (node (ref "R022") (pin "2") (pinfunction "2_2") (pintype "passive"))
    )
    (net (code "17") (name "Net-(C016-Pad2)") (class "Default")
      (node (ref "C016") (pin "2") (pinfunction "2_2") (pintype "passive"))
      (node (ref "C017") (pin "2") (pinfunction "2_2") (pintype "passive"))
      (node (ref "R024") (pin "2") (pinfunction "2_2") (pintype "passive"))
      (node (ref "R025") (pin "2") (pinfunction "2_2") (pintype "passive"))
    )
    (net (code "18") (name "Net-(C018-Pad2)") (class "Default")
      (node (ref "C018") (pin "2") (pinfunction "2_2") (pintype "passive"))
      (node (ref "C019") (pin "2") (pinfunction "2_2") (pintype "passive"))
      (node (ref "R033") (pin "2") (pinfunction "2_2") (pintype "passive"))
      (node (ref "R034") (pin "2") (pinfunction "2_2") (pintype "passive"))
    )
    (net (code "19") (name "Net-(C020-Pad2)") (class "Default")
      (node (ref "C020") (pin "2") (pinfunction "2_2") (pintype "passive"))
      (node (ref "C021") (pin "2") (pinfunction "2_2") (pintype "passive"))
      (node (ref "R037") (pin "2") (pinfunction "2_2") (pintype "passive"))
      (node (ref "R038") (pin "2") (pinfunction "2_2") (pintype "passive"))
    )
    (net (code "20") (name "Net-(C022-Pad2)") (class "Default")
      (node (ref "C022") (pin "2") (pinfunction "2_2") (pintype "passive"))
      (node (ref "R047") (pin "2") (pinfunction "2_2") (pintype "passive"))
    )
    (net (code "21") (name "Net-(C023-Pad2)") (class "Default")
      (node (ref "C023") (pin "2") (pinfunction "2_2") (pintype "passive"))
      (node (ref "R046") (pin "2") (pinfunction "2_2") (pintype "passive"))
    )
    (net (code "22") (name "Net-(C024-Pad2)") (class "Default")
      (node (ref "C024") (pin "2") (pinfunction "2_2") (pintype "passive"))
      (node (ref "R051") (pin "2") (pinfunction "2_2") (pintype "passive"))
    )
    (net (code "23") (name "Net-(C025-Pad2)") (class "Default")
      (node (ref "C025") (pin "2") (pinfunction "2_2") (pintype "passive"))
      (node (ref "R050") (pin "2") (pinfunction "2_2") (pintype "passive"))
    )
    (net (code "24") (name "Net-(CO11-Pad2)") (class "Default")
      (node (ref "CO11") (pin "2") (pinfunction "2_2") (pintype "passive"))
      (node (ref "R016") (pin "2") (pinfunction "2_2") (pintype "passive"))
      (node (ref "R017") (pin "1") (pinfunction "1_1") (pintype "passive"))
    )
    (net (code "25") (name "Net-(TR06-BOT)") (class "Default")
      (node (ref "R05") (pin "2") (pinfunction "2_2") (pintype "passive"))
      (node (ref "TR06") (pin "3") (pinfunction "BOT_3") (pintype "passive"))
    )
    (net (code "26") (name "Net-(TR06-TAP)") (class "Default")
      (node (ref "C003") (pin "1") (pinfunction "1_1") (pintype "passive"))
      (node (ref "C004") (pin "2") (pinfunction "2_2") (pintype "passive"))
      (node (ref "TR06") (pin "1") (pinfunction "TOP_1") (pintype "passive"))
      (node (ref "TR06") (pin "2") (pinfunction "TAP_2") (pintype "passive"))
      (node (ref "U02") (pin "6") (pinfunction "OUT_6") (pintype "output"))
    )
    (net (code "27") (name "Net-(TR07-BOT)") (class "Default")
      (node (ref "R010") (pin "2") (pinfunction "2_2") (pintype "passive"))
      (node (ref "TR07") (pin "3") (pinfunction "BOT_3") (pintype "passive"))
    )
    (net (code "28") (name "Net-(TR08-BOT)") (class "Default")
      (node (ref "R022") (pin "1") (pinfunction "1_1") (pintype "passive"))
      (node (ref "TR08") (pin "3") (pinfunction "BOT_3") (pintype "passive"))
    )
    (net (code "29") (name "Net-(TR09-BOT)") (class "Default")
      (node (ref "R025") (pin "1") (pinfunction "1_1") (pintype "passive"))
      (node (ref "TR09") (pin "3") (pinfunction "BOT_3") (pintype "passive"))
    )
    (net (code "30") (name "Net-(TR010-BOT)") (class "Default")
      (node (ref "R034") (pin "1") (pinfunction "1_1") (pintype "passive"))
      (node (ref "TR010") (pin "3") (pinfunction "BOT_3") (pintype "passive"))
    )
    (net (code "31") (name "Net-(TR011-BOT)") (class "Default")
      (node (ref "R038") (pin "1") (pinfunction "1_1") (pintype "passive"))
      (node (ref "TR011") (pin "3") (pinfunction "BOT_3") (pintype "passive"))
    )
    (net (code "32") (name "Net-(TR012-BOT)") (class "Default")
      (node (ref "R047") (pin "1") (pinfunction "1_1") (pintype "passive"))
      (node (ref "TR012") (pin "3") (pinfunction "BOT_3") (pintype "passive"))
    )
    (net (code "33") (name "Net-(TR013-BOT)") (class "Default")
      (node (ref "R051") (pin "1") (pinfunction "1_1") (pintype "passive"))
      (node (ref "TR013") (pin "3") (pinfunction "BOT_3") (pintype "passive"))
    )
    (net (code "34") (name "Net-(U01-IN-)") (class "Default")
      (node (ref "C001") (pin "2") (pinfunction "2_2") (pintype "passive"))
      (node (ref "R01") (pin "1") (pinfunction "1_1") (pintype "passive"))
      (node (ref "SIGNAL-IN") (pin "3") (pinfunction "3_3") (pintype "passive"))
      (node (ref "U01") (pin "2") (pinfunction "IN-_2") (pintype "input"))
    )
    (net (code "35") (name "Net-(U01-OUT)") (class "Default")
      (node (ref "C001") (pin "1") (pinfunction "1_1") (pintype "passive"))
      (node (ref "C002") (pin "2") (pinfunction "2_2") (pintype "passive"))
      (node (ref "R01") (pin "2") (pinfunction "2_2") (pintype "passive"))
      (node (ref "U01") (pin "6") (pinfunction "OUT_6") (pintype "output"))
    )
    (net (code "36") (name "Net-(U02-IN+)") (class "Default")
      (node (ref "R03") (pin "2") (pinfunction "2_2") (pintype "passive"))
      (node (ref "U02") (pin "3") (pinfunction "IN+_3") (pintype "input"))
    )
    (net (code "37") (name "Net-(U02-IN-)") (class "Default")
      (node (ref "C003") (pin "2") (pinfunction "2_2") (pintype "passive"))
      (node (ref "R04") (pin "2") (pinfunction "2_2") (pintype "passive"))
      (node (ref "R05") (pin "1") (pinfunction "1_1") (pintype "passive"))
      (node (ref "U02") (pin "2") (pinfunction "IN-_2") (pintype "input"))
    )
    (net (code "38") (name "Net-(U03-IN+)") (class "Default")
      (node (ref "R08") (pin "2") (pinfunction "2_2") (pintype "passive"))
      (node (ref "U03") (pin "3") (pinfunction "IN+_3") (pintype "input"))
    )
    (net (code "39") (name "Net-(U03-IN-)") (class "Default")
      (node (ref "C005") (pin "2") (pinfunction "2_2") (pintype "passive"))
      (node (ref "R010") (pin "1") (pinfunction "1_1") (pintype "passive"))
      (node (ref "R09") (pin "2") (pinfunction "2_2") (pintype "passive"))
      (node (ref "U03") (pin "2") (pinfunction "IN-_2") (pintype "input"))
    )
    (net (code "40") (name "Net-(U04-IN+)") (class "Default")
      (node (ref "C007") (pin "1") (pinfunction "1_1") (pintype "passive"))
      (node (ref "R012") (pin "2") (pinfunction "2_2") (pintype "passive"))
      (node (ref "U04") (pin "3") (pinfunction "IN+_3") (pintype "input"))
    )
    (net (code "41") (name "Net-(U04-IN-)") (class "Default")
      (node (ref "R013") (pin "1") (pinfunction "1_1") (pintype "passive"))
      (node (ref "R014") (pin "1") (pinfunction "1_1") (pintype "passive"))
      (node (ref "U04") (pin "2") (pinfunction "IN-_2") (pintype "input"))
      (node (ref "U04") (pin "6") (pinfunction "OUT_6") (pintype "output"))
    )
    (net (code "42") (name "Net-(U05-IN+)") (class "Default")
      (node (ref "C008") (pin "1") (pinfunction "1_1") (pintype "passive"))
      (node (ref "R015") (pin "1") (pinfunction "1_1") (pintype "passive"))
      (node (ref "U05") (pin "3") (pinfunction "IN+_3") (pintype "input"))
    )
    (net (code "43") (name "Net-(U05-IN-)") (class "Default")
      (node (ref "C009") (pin "1") (pinfunction "1_1") (pintype "passive"))
      (node (ref "R016") (pin "1") (pinfunction "1_1") (pintype "passive"))
      (node (ref "U05") (pin "2") (pinfunction "IN-_2") (pintype "input"))
      (node (ref "U05") (pin "6") (pinfunction "OUT_6") (pintype "output"))
    )
    (net (code "44") (name "Net-(U06-IN+)") (class "Default")
      (node (ref "CO10") (pin "2") (pinfunction "2_2") (pintype "passive"))
      (node (ref "R017") (pin "2") (pinfunction "2_2") (pintype "passive"))
      (node (ref "U06") (pin "3") (pinfunction "IN+_3") (pintype "input"))
    )
    (net (code "45") (name "Net-(U06-IN-)") (class "Default")
      (node (ref "CO11") (pin "1") (pinfunction "1_1") (pintype "passive"))
      (node (ref "R018") (pin "1") (pinfunction "1_1") (pintype "passive"))
      (node (ref "U06") (pin "2") (pinfunction "IN-_2") (pintype "input"))
      (node (ref "U06") (pin "6") (pinfunction "OUT_6") (pintype "output"))
    )
    (net (code "46") (name "Net-(U07-IN+)") (class "Default")
      (node (ref "CO12") (pin "2") (pinfunction "2_2") (pintype "passive"))
      (node (ref "R019") (pin "2") (pinfunction "2_2") (pintype "passive"))
      (node (ref "U07") (pin "3") (pinfunction "IN+_3") (pintype "input"))
    )
    (net (code "47") (name "Net-(U08-IN-)") (class "Default")
      (node (ref "C015") (pin "1") (pinfunction "1_1") (pintype "passive"))
      (node (ref "R021") (pin "1") (pinfunction "1_1") (pintype "passive"))
      (node (ref "U08") (pin "2") (pinfunction "IN-_2") (pintype "input"))
    )
    (net (code "48") (name "Net-(U08-OUT)") (class "Default")
      (node (ref "C014") (pin "1") (pinfunction "1_1") (pintype "passive"))
      (node (ref "R021") (pin "2") (pinfunction "2_2") (pintype "passive"))
      (node (ref "R024") (pin "1") (pinfunction "1_1") (pintype "passive"))
      (node (ref "U08") (pin "6") (pinfunction "OUT_6") (pintype "output"))
    )
    (net (code "49") (name "Net-(U09-IN-)") (class "Default")
      (node (ref "C017") (pin "1") (pinfunction "1_1") (pintype "passive"))
      (node (ref "R027") (pin "1") (pinfunction "1_1") (pintype "passive"))
      (node (ref "U09") (pin "2") (pinfunction "IN-_2") (pintype "input"))
    )
    (net (code "50") (name "Net-(U011-IN-)") (class "Default")
      (node (ref "C019") (pin "1") (pinfunction "1_1") (pintype "passive"))
      (node (ref "R036") (pin "1") (pinfunction "1_1") (pintype "passive"))
      (node (ref "U011") (pin "2") (pinfunction "IN-_2") (pintype "input"))
    )
    (net (code "51") (name "Net-(U011-OUT)") (class "Default")
      (node (ref "C018") (pin "1") (pinfunction "1_1") (pintype "passive"))
      (node (ref "R036") (pin "2") (pinfunction "2_2") (pintype "passive"))
      (node (ref "R037") (pin "1") (pinfunction "1_1") (pintype "passive"))
      (node (ref "U011") (pin "6") (pinfunction "OUT_6") (pintype "output"))
    )
    (net (code "52") (name "Net-(U012-IN-)") (class "Default")
      (node (ref "C021") (pin "1") (pinfunction "1_1") (pintype "passive"))
      (node (ref "R040") (pin "1") (pinfunction "1_1") (pintype "passive"))
      (node (ref "U012") (pin "2") (pinfunction "IN-_2") (pintype "input"))
    )
    (net (code "53") (name "Net-(U014-IN-)") (class "Default")
      (node (ref "C023") (pin "1") (pinfunction "1_1") (pintype "passive"))
      (node (ref "R049") (pin "1") (pinfunction "1_1") (pintype "passive"))
      (node (ref "U014") (pin "2") (pinfunction "IN-_2") (pintype "input"))
    )
    (net (code "54") (name "Net-(U014-OUT)") (class "Default")
      (node (ref "C022") (pin "1") (pinfunction "1_1") (pintype "passive"))
      (node (ref "R049") (pin "2") (pinfunction "2_2") (pintype "passive"))
      (node (ref "R050") (pin "1") (pinfunction "1_1") (pintype "passive"))
      (node (ref "U014") (pin "6") (pinfunction "OUT_6") (pintype "output"))
    )
    (net (code "55") (name "Net-(U015-IN-)") (class "Default")
      (node (ref "C025") (pin "1") (pinfunction "1_1") (pintype "passive"))
      (node (ref "R053") (pin "1") (pinfunction "1_1") (pintype "passive"))
      (node (ref "U015") (pin "2") (pinfunction "IN-_2") (pintype "input"))
    )
    (net (code "56") (name "unconnected-(U01-BAL-Pad1)") (class "Default")
      (node (ref "U01") (pin "1") (pinfunction "BAL_1") (pintype "passive+no_connect"))
    )
    (net (code "57") (name "unconnected-(U01-BAL-Pad8)") (class "Default")
      (node (ref "U01") (pin "8") (pinfunction "BAL_8") (pintype "passive+no_connect"))
    )
    (net (code "58") (name "unconnected-(U01-NC-Pad5)") (class "Default")
      (node (ref "U01") (pin "5") (pinfunction "NC_5") (pintype "passive+no_connect"))
    )
    (net (code "59") (name "unconnected-(U02-NC-Pad5)") (class "Default")
      (node (ref "U02") (pin "5") (pinfunction "NC_5") (pintype "passive+no_connect"))
    )
    (net (code "60") (name "unconnected-(U02-VOSTRIM-Pad1)") (class "Default")
      (node (ref "U02") (pin "1") (pinfunction "VOSTRIM_1") (pintype "passive+no_connect"))
    )
    (net (code "61") (name "unconnected-(U02-VOSTRIM-Pad8)") (class "Default")
      (node (ref "U02") (pin "8") (pinfunction "VOSTRIM_8") (pintype "passive+no_connect"))
    )
    (net (code "62") (name "unconnected-(U03-NC-Pad5)") (class "Default")
      (node (ref "U03") (pin "5") (pinfunction "NC_5") (pintype "passive+no_connect"))
    )
    (net (code "63") (name "unconnected-(U03-VOSTRIM-Pad1)") (class "Default")
      (node (ref "U03") (pin "1") (pinfunction "VOSTRIM_1") (pintype "passive+no_connect"))
    )
    (net (code "64") (name "unconnected-(U03-VOSTRIM-Pad8)") (class "Default")
      (node (ref "U03") (pin "8") (pinfunction "VOSTRIM_8") (pintype "passive+no_connect"))
    )
    (net (code "65") (name "unconnected-(U04-NC-Pad5)") (class "Default")
      (node (ref "U04") (pin "5") (pinfunction "NC_5") (pintype "passive+no_connect"))
    )
    (net (code "66") (name "unconnected-(U04-VOSTRIM-Pad1)") (class "Default")
      (node (ref "U04") (pin "1") (pinfunction "VOSTRIM_1") (pintype "passive+no_connect"))
    )
    (net (code "67") (name "unconnected-(U04-VOSTRIM-Pad8)") (class "Default")
      (node (ref "U04") (pin "8") (pinfunction "VOSTRIM_8") (pintype "passive+no_connect"))
    )
    (net (code "68") (name "unconnected-(U05-NC-Pad5)") (class "Default")
      (node (ref "U05") (pin "5") (pinfunction "NC_5") (pintype "passive+no_connect"))
    )
    (net (code "69") (name "unconnected-(U05-VOSTRIM-Pad1)") (class "Default")
      (node (ref "U05") (pin "1") (pinfunction "VOSTRIM_1") (pintype "passive+no_connect"))
    )
    (net (code "70") (name "unconnected-(U05-VOSTRIM-Pad8)") (class "Default")
      (node (ref "U05") (pin "8") (pinfunction "VOSTRIM_8") (pintype "passive+no_connect"))
    )
    (net (code "71") (name "unconnected-(U06-NC-Pad5)") (class "Default")
      (node (ref "U06") (pin "5") (pinfunction "NC_5") (pintype "passive+no_connect"))
    )
    (net (code "72") (name "unconnected-(U06-VOSTRIM-Pad1)") (class "Default")
      (node (ref "U06") (pin "1") (pinfunction "VOSTRIM_1") (pintype "passive+no_connect"))
    )
    (net (code "73") (name "unconnected-(U06-VOSTRIM-Pad8)") (class "Default")
      (node (ref "U06") (pin "8") (pinfunction "VOSTRIM_8") (pintype "passive+no_connect"))
    )
    (net (code "74") (name "unconnected-(U07-NC-Pad5)") (class "Default")
      (node (ref "U07") (pin "5") (pinfunction "NC_5") (pintype "passive+no_connect"))
    )
    (net (code "75") (name "unconnected-(U07-VOSTRIM-Pad1)") (class "Default")
      (node (ref "U07") (pin "1") (pinfunction "VOSTRIM_1") (pintype "passive+no_connect"))
    )
    (net (code "76") (name "unconnected-(U07-VOSTRIM-Pad8)") (class "Default")
      (node (ref "U07") (pin "8") (pinfunction "VOSTRIM_8") (pintype "passive+no_connect"))
    )
    (net (code "77") (name "unconnected-(U08-NC-Pad5)") (class "Default")
      (node (ref "U08") (pin "5") (pinfunction "NC_5") (pintype "passive+no_connect"))
    )
    (net (code "78") (name "unconnected-(U08-VOSTRIM-Pad1)") (class "Default")
      (node (ref "U08") (pin "1") (pinfunction "VOSTRIM_1") (pintype "passive+no_connect"))
    )
    (net (code "79") (name "unconnected-(U08-VOSTRIM-Pad8)") (class "Default")
      (node (ref "U08") (pin "8") (pinfunction "VOSTRIM_8") (pintype "passive+no_connect"))
    )
    (net (code "80") (name "unconnected-(U09-NC-Pad5)") (class "Default")
      (node (ref "U09") (pin "5") (pinfunction "NC_5") (pintype "passive+no_connect"))
    )
    (net (code "81") (name "unconnected-(U09-VOSTRIM-Pad1)") (class "Default")
      (node (ref "U09") (pin "1") (pinfunction "VOSTRIM_1") (pintype "passive+no_connect"))
    )
    (net (code "82") (name "unconnected-(U09-VOSTRIM-Pad8)") (class "Default")
      (node (ref "U09") (pin "8") (pinfunction "VOSTRIM_8") (pintype "passive+no_connect"))
    )
    (net (code "83") (name "unconnected-(U011-NC-Pad5)") (class "Default")
      (node (ref "U011") (pin "5") (pinfunction "NC_5") (pintype "passive+no_connect"))
    )
    (net (code "84") (name "unconnected-(U011-VOSTRIM-Pad1)") (class "Default")
      (node (ref "U011") (pin "1") (pinfunction "VOSTRIM_1") (pintype "passive+no_connect"))
    )
    (net (code "85") (name "unconnected-(U011-VOSTRIM-Pad8)") (class "Default")
      (node (ref "U011") (pin "8") (pinfunction "VOSTRIM_8") (pintype "passive+no_connect"))
    )
    (net (code "86") (name "unconnected-(U012-NC-Pad5)") (class "Default")
      (node (ref "U012") (pin "5") (pinfunction "NC_5") (pintype "passive+no_connect"))
    )
    (net (code "87") (name "unconnected-(U012-VOSTRIM-Pad1)") (class "Default")
      (node (ref "U012") (pin "1") (pinfunction "VOSTRIM_1") (pintype "passive+no_connect"))
    )
    (net (code "88") (name "unconnected-(U012-VOSTRIM-Pad8)") (class "Default")
      (node (ref "U012") (pin "8") (pinfunction "VOSTRIM_8") (pintype "passive+no_connect"))
    )
    (net (code "89") (name "unconnected-(U014-NC-Pad5)") (class "Default")
      (node (ref "U014") (pin "5") (pinfunction "NC_5") (pintype "passive+no_connect"))
    )
    (net (code "90") (name "unconnected-(U014-VOSTRIM-Pad1)") (class "Default")
      (node (ref "U014") (pin "1") (pinfunction "VOSTRIM_1") (pintype "passive+no_connect"))
    )
    (net (code "91") (name "unconnected-(U014-VOSTRIM-Pad8)") (class "Default")
      (node (ref "U014") (pin "8") (pinfunction "VOSTRIM_8") (pintype "passive+no_connect"))
    )
    (net (code "92") (name "unconnected-(U015-NC-Pad5)") (class "Default")
      (node (ref "U015") (pin "5") (pinfunction "NC_5") (pintype "passive+no_connect"))
    )
    (net (code "93") (name "unconnected-(U015-VOSTRIM-Pad1)") (class "Default")
      (node (ref "U015") (pin "1") (pinfunction "VOSTRIM_1") (pintype "passive+no_connect"))
    )
    (net (code "94") (name "unconnected-(U015-VOSTRIM-Pad8)") (class "Default")
      (node (ref "U015") (pin "8") (pinfunction "VOSTRIM_8") (pintype "passive+no_connect"))
    )
  )
)
